# EVB-NORA-B2_SCHEM_0006_PinHeaders_ULED.net
KiCad netlist of a schematic drawn in Altium Designer
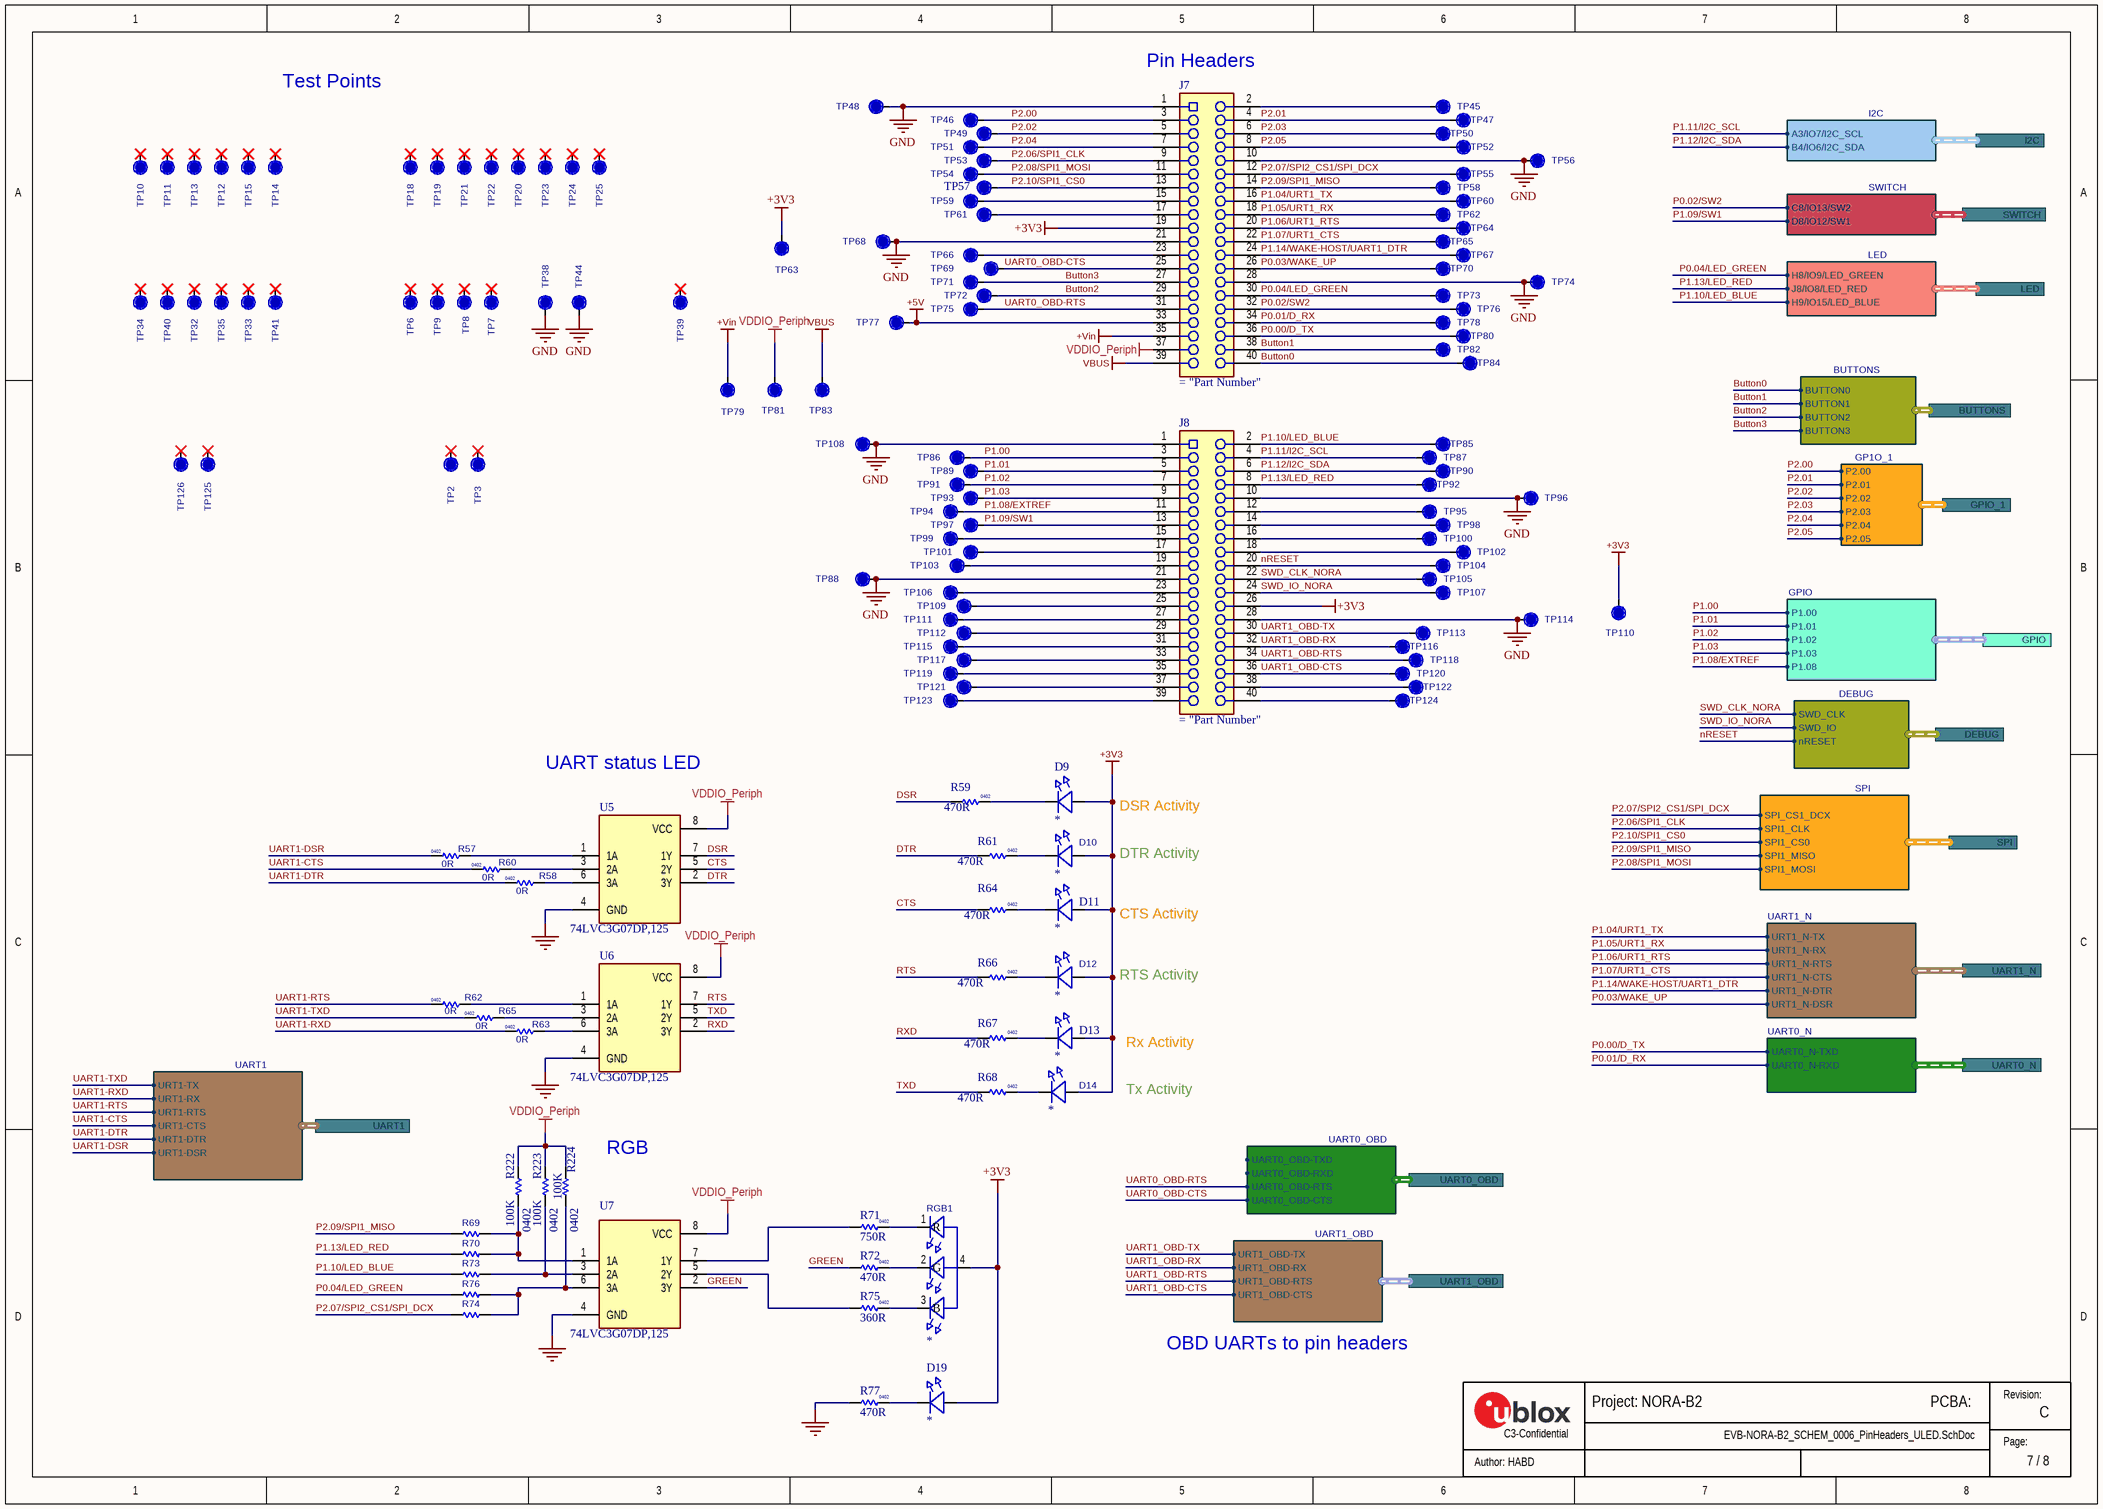
[diagram p0: EVB-NORA-B2_SCHEM_0006_PinHeaders_ULED.SchDoc]

(export (version "E")
  (design (tool "Eeschema 10.0.6"))
  (components
    (comp (ref "D9")
      (value "UBXH11-0000057")
      (footprint "LED_0603_YELLOW")
      (description "DIODE LED SMT YELLOW CLEAR LENS 2.1V 10MA 0603 YELLOW")
      (fields
        (field (name "COLOR") "*")
        (field (name "MANUFACTURER") "Lite-on Technology Corporation")
        (field (name "EDITOR") "eric.moog")
      )
      (libsource (lib "UBX_Parts_DB_Lib") (part "LED_BASE"))
    )
    (comp (ref "D10")
      (value "UBXH11-0000001")
      (footprint "LED_0603_GREEN")
      (description "LED SMD 0603 GREEN 2.5V 20mA")
      (fields
        (field (name "COLOR") "*")
        (field (name "MANUFACTURER") "Kingbright")
        (field (name "EDITOR") "gianni.falleroni")
        (field (name "RELEASED BY") "alex.claville")
      )
      (libsource (lib "UBX_Parts_DB_Lib") (part "LED_BASE"))
    )
    (comp (ref "D11")
      (value "UBXH11-0000057")
      (footprint "LED_0603_YELLOW")
      (description "DIODE LED SMT YELLOW CLEAR LENS 2.1V 10MA 0603 YELLOW")
      (fields
        (field (name "COLOR") "*")
        (field (name "MANUFACTURER") "Lite-on Technology Corporation")
        (field (name "EDITOR") "eric.moog")
      )
      (libsource (lib "UBX_Parts_DB_Lib") (part "LED_BASE"))
    )
    (comp (ref "D12")
      (value "UBXH11-0000001")
      (footprint "LED_0603_GREEN")
      (description "LED SMD 0603 GREEN 2.5V 20mA")
      (fields
        (field (name "COLOR") "*")
        (field (name "MANUFACTURER") "Kingbright")
        (field (name "EDITOR") "gianni.falleroni")
        (field (name "RELEASED BY") "alex.claville")
      )
      (libsource (lib "UBX_Parts_DB_Lib") (part "LED_BASE"))
    )
    (comp (ref "D13")
      (value "UBXH11-0000057")
      (footprint "LED_0603_YELLOW")
      (description "DIODE LED SMT YELLOW CLEAR LENS 2.1V 10MA 0603 YELLOW")
      (fields
        (field (name "COLOR") "*")
        (field (name "MANUFACTURER") "Lite-on Technology Corporation")
        (field (name "EDITOR") "eric.moog")
      )
      (libsource (lib "UBX_Parts_DB_Lib") (part "LED_BASE"))
    )
    (comp (ref "D14")
      (value "UBXH11-0000001")
      (footprint "LED_0603_GREEN")
      (description "LED SMD 0603 GREEN 2.5V 20mA")
      (fields
        (field (name "COLOR") "*")
        (field (name "MANUFACTURER") "Kingbright")
        (field (name "EDITOR") "gianni.falleroni")
        (field (name "RELEASED BY") "alex.claville")
      )
      (libsource (lib "UBX_Parts_DB_Lib") (part "LED_BASE"))
    )
    (comp (ref "D19")
      (value "UBXH11-0000018")
      (footprint "LED_0603_1600Lx800Wx400H_600x800Pad_800G_FLX")
      (description "LED CHIP 0603 LOW CURRENT OSRAM 0.002A GREEN 2.2V 2mA")
      (fields
        (field (name "COLOR") "*")
        (field (name "MANUFACTURER") "Osram")
        (field (name "EDITOR") "johann.furrer")
        (field (name "RELEASED BY") "martin.grasse")
      )
      (libsource (lib "UBX_Parts_DB_Lib") (part "LED_BASE"))
    )
    (comp (ref "J7")
      (value "~")
      (footprint "M208762042")
      (description "Connector")
      (fields
        (field (name "MANUFACTURER_PART_NUMBER") "M20-8762042")
        (field (name "MOUSER PART NUMBER") "855-M20-8762042")
      )
      (libsource (lib "SamacSys") (part "M20-8762042"))
    )
    (comp (ref "J8")
      (value "~")
      (footprint "M208762042")
      (description "Connector")
      (fields
        (field (name "MANUFACTURER_PART_NUMBER") "M20-8762042")
        (field (name "MOUSER PART NUMBER") "855-M20-8762042")
      )
      (libsource (lib "SamacSys") (part "M20-8762042"))
    )
    (comp (ref "R57")
      (value "0R")
      (footprint "RES 0402 HD")
      (description "RES THICK FILM CHIP 0402 0R 0 100mW")
      (fields
        (field (name "SIZE") "0402")
        (field (name "PART NUMBER") "UBXH18-0003002")
        (field (name "TOLERANCE") "0")
        (field (name "EDITOR") "charlotte.biber")
        (field (name "RELEASED BY") "peter.mueller")
      )
      (libsource (lib "UBX_Parts_DB_Lib") (part "Res sm"))
    )
    (comp (ref "R58")
      (value "0R")
      (footprint "RES 0402 HD")
      (description "RES THICK FILM CHIP 0402 0R 0 100mW")
      (fields
        (field (name "SIZE") "0402")
        (field (name "PART NUMBER") "UBXH18-0003002")
        (field (name "TOLERANCE") "0")
        (field (name "EDITOR") "charlotte.biber")
        (field (name "RELEASED BY") "peter.mueller")
      )
      (libsource (lib "UBX_Parts_DB_Lib") (part "Res sm"))
    )
    (comp (ref "R59")
      (value "470R")
      (footprint "RES_0402_1100Lx600Wx400H_500x600Pad_400G_FLX")
      (description "RES THICK FILM CHIP 0402 470R 5% 100mW")
      (fields
        (field (name "SIZE") "0402")
        (field (name "PART NUMBER") "UBXH18-0008041")
        (field (name "TOLERANCE") "5%")
        (field (name "EDITOR") "roland.rust")
        (field (name "RELEASED BY") "roland.rust")
      )
      (libsource (lib "UBX_Parts_DB_Lib") (part "Res sm"))
    )
    (comp (ref "R60")
      (value "0R")
      (footprint "RES 0402 HD")
      (description "RES THICK FILM CHIP 0402 0R 0 100mW")
      (fields
        (field (name "SIZE") "0402")
        (field (name "PART NUMBER") "UBXH18-0003002")
        (field (name "TOLERANCE") "0")
        (field (name "EDITOR") "charlotte.biber")
        (field (name "RELEASED BY") "peter.mueller")
      )
      (libsource (lib "UBX_Parts_DB_Lib") (part "Res sm"))
    )
    (comp (ref "R61")
      (value "470R")
      (footprint "RES_0402_1100Lx600Wx400H_500x600Pad_400G_FLX")
      (description "RES THICK FILM CHIP 0402 470R 5% 100mW")
      (fields
        (field (name "SIZE") "0402")
        (field (name "PART NUMBER") "UBXH18-0008041")
        (field (name "TOLERANCE") "5%")
        (field (name "EDITOR") "roland.rust")
        (field (name "RELEASED BY") "roland.rust")
      )
      (libsource (lib "UBX_Parts_DB_Lib") (part "Res sm"))
    )
    (comp (ref "R62")
      (value "0R")
      (footprint "RES 0402 HD")
      (description "RES THICK FILM CHIP 0402 0R 0 100mW")
      (fields
        (field (name "SIZE") "0402")
        (field (name "PART NUMBER") "UBXH18-0003002")
        (field (name "TOLERANCE") "0")
        (field (name "EDITOR") "charlotte.biber")
        (field (name "RELEASED BY") "peter.mueller")
      )
      (libsource (lib "UBX_Parts_DB_Lib") (part "Res sm"))
    )
    (comp (ref "R63")
      (value "0R")
      (footprint "RES 0402 HD")
      (description "RES THICK FILM CHIP 0402 0R 0 100mW")
      (fields
        (field (name "SIZE") "0402")
        (field (name "PART NUMBER") "UBXH18-0003002")
        (field (name "TOLERANCE") "0")
        (field (name "EDITOR") "charlotte.biber")
        (field (name "RELEASED BY") "peter.mueller")
      )
      (libsource (lib "UBX_Parts_DB_Lib") (part "Res sm"))
    )
    (comp (ref "R64")
      (value "470R")
      (footprint "RES_0402_1100Lx600Wx400H_500x600Pad_400G_FLX")
      (description "RES THICK FILM CHIP 0402 470R 5% 100mW")
      (fields
        (field (name "SIZE") "0402")
        (field (name "PART NUMBER") "UBXH18-0008041")
        (field (name "TOLERANCE") "5%")
        (field (name "EDITOR") "roland.rust")
        (field (name "RELEASED BY") "roland.rust")
      )
      (libsource (lib "UBX_Parts_DB_Lib") (part "Res sm"))
    )
    (comp (ref "R65")
      (value "0R")
      (footprint "RES 0402 HD")
      (description "RES THICK FILM CHIP 0402 0R 0 100mW")
      (fields
        (field (name "SIZE") "0402")
        (field (name "PART NUMBER") "UBXH18-0003002")
        (field (name "TOLERANCE") "0")
        (field (name "EDITOR") "charlotte.biber")
        (field (name "RELEASED BY") "peter.mueller")
      )
      (libsource (lib "UBX_Parts_DB_Lib") (part "Res sm"))
    )
    (comp (ref "R66")
      (value "470R")
      (footprint "RES_0402_1100Lx600Wx400H_500x600Pad_400G_FLX")
      (description "RES THICK FILM CHIP 0402 470R 5% 100mW")
      (fields
        (field (name "SIZE") "0402")
        (field (name "PART NUMBER") "UBXH18-0008041")
        (field (name "TOLERANCE") "5%")
        (field (name "EDITOR") "roland.rust")
        (field (name "RELEASED BY") "roland.rust")
      )
      (libsource (lib "UBX_Parts_DB_Lib") (part "Res sm"))
    )
    (comp (ref "R67")
      (value "470R")
      (footprint "RES_0402_1100Lx600Wx400H_500x600Pad_400G_FLX")
      (description "RES THICK FILM CHIP 0402 470R 5% 100mW")
      (fields
        (field (name "SIZE") "0402")
        (field (name "PART NUMBER") "UBXH18-0008041")
        (field (name "TOLERANCE") "5%")
        (field (name "EDITOR") "roland.rust")
        (field (name "RELEASED BY") "roland.rust")
      )
      (libsource (lib "UBX_Parts_DB_Lib") (part "Res sm"))
    )
    (comp (ref "R68")
      (value "470R")
      (footprint "RES_0402_1100Lx600Wx400H_500x600Pad_400G_FLX")
      (description "RES THICK FILM CHIP 0402 470R 5% 100mW")
      (fields
        (field (name "SIZE") "0402")
        (field (name "PART NUMBER") "UBXH18-0008041")
        (field (name "TOLERANCE") "5%")
        (field (name "EDITOR") "roland.rust")
        (field (name "RELEASED BY") "roland.rust")
      )
      (libsource (lib "UBX_Parts_DB_Lib") (part "Res sm"))
    )
    (comp (ref "R69")
      (value "UBXH18-0003002")
      (footprint "RES 0402 HD")
      (description "RES THICK FILM CHIP 0402 0R 0 100mW")
      (fields
        (field (name "TOLERANCE") "0")
        (field (name "MANUFACTURER") "KOA")
        (field (name "EDITOR") "charlotte.biber")
        (field (name "RELEASED BY") "peter.mueller")
      )
      (libsource (lib "UBX_Parts_DB_Lib") (part "Res sm"))
    )
    (comp (ref "R70")
      (value "UBXH18-0003002")
      (footprint "RES 0402 HD")
      (description "RES THICK FILM CHIP 0402 0R 0 100mW")
      (fields
        (field (name "TOLERANCE") "0")
        (field (name "MANUFACTURER") "KOA")
        (field (name "EDITOR") "charlotte.biber")
        (field (name "RELEASED BY") "peter.mueller")
      )
      (libsource (lib "UBX_Parts_DB_Lib") (part "Res sm"))
    )
    (comp (ref "R71")
      (value "750R")
      (footprint "RES_0402_1100Lx600Wx400H_500x600Pad_400G_FLX")
      (description "RES THICK FILM CHIP 0402 750R 5% 100mW")
      (fields
        (field (name "SIZE") "0402")
        (field (name "PART NUMBER") "UBXH18-0008046")
        (field (name "TOLERANCE") "5%")
        (field (name "EDITOR") "jaka.bevk")
        (field (name "RELEASED BY") "erian.bezhani")
      )
      (libsource (lib "UBX_Parts_DB_Lib") (part "Res sm"))
    )
    (comp (ref "R72")
      (value "470R")
      (footprint "RES_0402_1100Lx600Wx400H_500x600Pad_400G_FLX")
      (description "RES THICK FILM CHIP 0402 470R 5% 100mW")
      (fields
        (field (name "SIZE") "0402")
        (field (name "PART NUMBER") "UBXH18-0008041")
        (field (name "TOLERANCE") "5%")
        (field (name "EDITOR") "roland.rust")
        (field (name "RELEASED BY") "roland.rust")
      )
      (libsource (lib "UBX_Parts_DB_Lib") (part "Res sm"))
    )
    (comp (ref "R73")
      (value "UBXH18-0003002")
      (footprint "RES 0402 HD")
      (description "RES THICK FILM CHIP 0402 0R 0 100mW")
      (fields
        (field (name "TOLERANCE") "0")
        (field (name "MANUFACTURER") "KOA")
        (field (name "EDITOR") "charlotte.biber")
        (field (name "RELEASED BY") "peter.mueller")
      )
      (libsource (lib "UBX_Parts_DB_Lib") (part "Res sm"))
    )
    (comp (ref "R74")
      (value "UBXH18-0003002")
      (footprint "RES 0402 HD")
      (description "RES THICK FILM CHIP 0402 0R 0 100mW")
      (fields
        (field (name "TOLERANCE") "0")
        (field (name "MANUFACTURER") "KOA")
        (field (name "EDITOR") "charlotte.biber")
        (field (name "RELEASED BY") "peter.mueller")
      )
      (libsource (lib "UBX_Parts_DB_Lib") (part "Res sm"))
    )
    (comp (ref "R75")
      (value "360R")
      (footprint "RES_0402_1100Lx600Wx400H_500x600Pad_400G_FLX")
      (description "RES THICK FILM CHIP 0402 360R 1% 63mW")
      (fields
        (field (name "SIZE") "0402")
        (field (name "PART NUMBER") "UBXH18-0000216")
        (field (name "TOLERANCE") "1%")
        (field (name "EDITOR") "michael.hein")
        (field (name "RELEASED BY") "vasyl.dykyy")
      )
      (libsource (lib "UBX_Parts_DB_Lib") (part "Res sm"))
    )
    (comp (ref "R76")
      (value "UBXH18-0003002")
      (footprint "RES 0402 HD")
      (description "RES THICK FILM CHIP 0402 0R 0 100mW")
      (fields
        (field (name "TOLERANCE") "0")
        (field (name "MANUFACTURER") "KOA")
        (field (name "EDITOR") "charlotte.biber")
        (field (name "RELEASED BY") "peter.mueller")
      )
      (libsource (lib "UBX_Parts_DB_Lib") (part "Res sm"))
    )
    (comp (ref "R77")
      (value "470R")
      (footprint "RES_0402_1100Lx600Wx400H_500x600Pad_400G_FLX")
      (description "RES THICK FILM CHIP 0402 470R 5% 100mW")
      (fields
        (field (name "SIZE") "0402")
        (field (name "PART NUMBER") "UBXH18-0008041")
        (field (name "TOLERANCE") "5%")
        (field (name "EDITOR") "roland.rust")
        (field (name "RELEASED BY") "roland.rust")
      )
      (libsource (lib "UBX_Parts_DB_Lib") (part "Res sm"))
    )
    (comp (ref "R222")
      (value "100K")
      (footprint "RES 0402 HD")
      (description "RES THICK FILM CHIP 0402 100K 1% 63mW")
      (fields
        (field (name "SIZE") "0402")
        (field (name "PART NUMBER") "UBXH18-0000005")
        (field (name "TOLERANCE") "1%")
        (field (name "EDITOR") "dario.antonaz")
        (field (name "RELEASED BY") "sandro.sestan")
      )
      (libsource (lib "UBX_Parts_DB_Lib") (part "Res sm"))
    )
    (comp (ref "R223")
      (value "100K")
      (footprint "RES 0402 HD")
      (description "RES THICK FILM CHIP 0402 100K 1% 63mW")
      (fields
        (field (name "SIZE") "0402")
        (field (name "PART NUMBER") "UBXH18-0000005")
        (field (name "TOLERANCE") "1%")
        (field (name "EDITOR") "dario.antonaz")
        (field (name "RELEASED BY") "sandro.sestan")
      )
      (libsource (lib "UBX_Parts_DB_Lib") (part "Res sm"))
    )
    (comp (ref "R224")
      (value "100K")
      (footprint "RES 0402 HD")
      (description "RES THICK FILM CHIP 0402 100K 1% 63mW")
      (fields
        (field (name "SIZE") "0402")
        (field (name "PART NUMBER") "UBXH18-0000005")
        (field (name "TOLERANCE") "1%")
        (field (name "EDITOR") "dario.antonaz")
        (field (name "RELEASED BY") "sandro.sestan")
      )
      (libsource (lib "UBX_Parts_DB_Lib") (part "Res sm"))
    )
    (comp (ref "RGB1")
      (value "115-00026")
      (footprint "LED_1616")
      (description "LED RGB SMT 0606")
      (fields (field (name "COLOR") "*") (field (name "VOLTAGE") "None"))
      (libsource (lib "Arena_Parts_DB_Lib") (part "LED_RGB_CA_4"))
    )
    (comp (ref "TP2")
      (value "TP10R")
      (footprint "TP10R")
      (description "Testpoint, Round 1.0mm Dia")
      (fields (field (name "ADDED BY") "Jeremy D") (field (name "CHECKED BY") "Paul B"))
      (libsource (lib "LEGACY_Rigado_AltiumLib") (part "TP_R"))
    )
    (comp (ref "TP3")
      (value "TP10R")
      (footprint "TP10R")
      (description "Testpoint, Round 1.0mm Dia")
      (fields (field (name "ADDED BY") "Jeremy D") (field (name "CHECKED BY") "Paul B"))
      (libsource (lib "LEGACY_Rigado_AltiumLib") (part "TP_R"))
    )
    (comp (ref "TP6")
      (value "TP10R")
      (footprint "TP10R")
      (description "Testpoint, Round 1.0mm Dia")
      (fields (field (name "ADDED BY") "Jeremy D") (field (name "CHECKED BY") "Paul B"))
      (libsource (lib "") (part "TP_R_1"))
    )
    (comp (ref "TP7")
      (value "TP10R")
      (footprint "TP10R")
      (description "Testpoint, Round 1.0mm Dia")
      (fields (field (name "ADDED BY") "Jeremy D") (field (name "CHECKED BY") "Paul B"))
      (libsource (lib "LEGACY_Rigado_AltiumLib") (part "TP_R"))
    )
    (comp (ref "TP8")
      (value "TP10R")
      (footprint "TP10R")
      (description "Testpoint, Round 1.0mm Dia")
      (fields (field (name "ADDED BY") "Jeremy D") (field (name "CHECKED BY") "Paul B"))
      (libsource (lib "LEGACY_Rigado_AltiumLib") (part "TP_R"))
    )
    (comp (ref "TP9")
      (value "TP10R")
      (footprint "TP10R")
      (description "Testpoint, Round 1.0mm Dia")
      (fields (field (name "ADDED BY") "Jeremy D") (field (name "CHECKED BY") "Paul B"))
      (libsource (lib "LEGACY_Rigado_AltiumLib") (part "TP_R"))
    )
    (comp (ref "TP10")
      (value "TP10R")
      (footprint "TP10R")
      (description "Testpoint, Round 1.0mm Dia")
      (fields (field (name "ADDED BY") "Jeremy D") (field (name "CHECKED BY") "Paul B"))
      (libsource (lib "LEGACY_Rigado_AltiumLib") (part "TP_R"))
    )
    (comp (ref "TP11")
      (value "TP10R")
      (footprint "TP10R")
      (description "Testpoint, Round 1.0mm Dia")
      (fields (field (name "ADDED BY") "Jeremy D") (field (name "CHECKED BY") "Paul B"))
      (libsource (lib "LEGACY_Rigado_AltiumLib") (part "TP_R"))
    )
    (comp (ref "TP12")
      (value "TP10R")
      (footprint "TP10R")
      (description "Testpoint, Round 1.0mm Dia")
      (fields (field (name "ADDED BY") "Jeremy D") (field (name "CHECKED BY") "Paul B"))
      (libsource (lib "LEGACY_Rigado_AltiumLib") (part "TP_R"))
    )
    (comp (ref "TP13")
      (value "TP10R")
      (footprint "TP10R")
      (description "Testpoint, Round 1.0mm Dia")
      (fields (field (name "ADDED BY") "Jeremy D") (field (name "CHECKED BY") "Paul B"))
      (libsource (lib "LEGACY_Rigado_AltiumLib") (part "TP_R"))
    )
    (comp (ref "TP14")
      (value "TP10R")
      (footprint "TP10R")
      (description "Testpoint, Round 1.0mm Dia")
      (fields (field (name "ADDED BY") "Jeremy D") (field (name "CHECKED BY") "Paul B"))
      (libsource (lib "LEGACY_Rigado_AltiumLib") (part "TP_R"))
    )
    (comp (ref "TP15")
      (value "TP10R")
      (footprint "TP10R")
      (description "Testpoint, Round 1.0mm Dia")
      (fields (field (name "ADDED BY") "Jeremy D") (field (name "CHECKED BY") "Paul B"))
      (libsource (lib "LEGACY_Rigado_AltiumLib") (part "TP_R"))
    )
    (comp (ref "TP18")
      (value "TP10R")
      (footprint "TP10R")
      (description "Testpoint, Round 1.0mm Dia")
      (fields (field (name "ADDED BY") "Jeremy D") (field (name "CHECKED BY") "Paul B"))
      (libsource (lib "LEGACY_Rigado_AltiumLib") (part "TP_R"))
    )
    (comp (ref "TP19")
      (value "TP10R")
      (footprint "TP10R")
      (description "Testpoint, Round 1.0mm Dia")
      (fields (field (name "ADDED BY") "Jeremy D") (field (name "CHECKED BY") "Paul B"))
      (libsource (lib "LEGACY_Rigado_AltiumLib") (part "TP_R"))
    )
    (comp (ref "TP20")
      (value "TP10R")
      (footprint "TP10R")
      (description "Testpoint, Round 1.0mm Dia")
      (fields (field (name "ADDED BY") "Jeremy D") (field (name "CHECKED BY") "Paul B"))
      (libsource (lib "LEGACY_Rigado_AltiumLib") (part "TP_R"))
    )
    (comp (ref "TP21")
      (value "TP10R")
      (footprint "TP10R")
      (description "Testpoint, Round 1.0mm Dia")
      (fields (field (name "ADDED BY") "Jeremy D") (field (name "CHECKED BY") "Paul B"))
      (libsource (lib "LEGACY_Rigado_AltiumLib") (part "TP_R"))
    )
    (comp (ref "TP22")
      (value "TP10R")
      (footprint "TP10R")
      (description "Testpoint, Round 1.0mm Dia")
      (fields (field (name "ADDED BY") "Jeremy D") (field (name "CHECKED BY") "Paul B"))
      (libsource (lib "LEGACY_Rigado_AltiumLib") (part "TP_R"))
    )
    (comp (ref "TP23")
      (value "TP10R")
      (footprint "TP10R")
      (description "Testpoint, Round 1.0mm Dia")
      (fields (field (name "ADDED BY") "Jeremy D") (field (name "CHECKED BY") "Paul B"))
      (libsource (lib "LEGACY_Rigado_AltiumLib") (part "TP_R"))
    )
    (comp (ref "TP24")
      (value "TP10R")
      (footprint "TP10R")
      (description "Testpoint, Round 1.0mm Dia")
      (fields (field (name "ADDED BY") "Jeremy D") (field (name "CHECKED BY") "Paul B"))
      (libsource (lib "LEGACY_Rigado_AltiumLib") (part "TP_R"))
    )
    (comp (ref "TP25")
      (value "TP10R")
      (footprint "TP10R")
      (description "Testpoint, Round 1.0mm Dia")
      (fields (field (name "ADDED BY") "Jeremy D") (field (name "CHECKED BY") "Paul B"))
      (libsource (lib "LEGACY_Rigado_AltiumLib") (part "TP_R"))
    )
    (comp (ref "TP32")
      (value "TP10R")
      (footprint "TP10R")
      (description "Testpoint, Round 1.0mm Dia")
      (fields (field (name "ADDED BY") "Jeremy D") (field (name "CHECKED BY") "Paul B"))
      (libsource (lib "LEGACY_Rigado_AltiumLib") (part "TP_R"))
    )
    (comp (ref "TP33")
      (value "TP10R")
      (footprint "TP10R")
      (description "Testpoint, Round 1.0mm Dia")
      (fields (field (name "ADDED BY") "Jeremy D") (field (name "CHECKED BY") "Paul B"))
      (libsource (lib "LEGACY_Rigado_AltiumLib") (part "TP_R"))
    )
    (comp (ref "TP34")
      (value "TP10R")
      (footprint "TP10R")
      (description "Testpoint, Round 1.0mm Dia")
      (fields (field (name "ADDED BY") "Jeremy D") (field (name "CHECKED BY") "Paul B"))
      (libsource (lib "LEGACY_Rigado_AltiumLib") (part "TP_R"))
    )
    (comp (ref "TP35")
      (value "TP10R")
      (footprint "TP10R")
      (description "Testpoint, Round 1.0mm Dia")
      (fields (field (name "ADDED BY") "Jeremy D") (field (name "CHECKED BY") "Paul B"))
      (libsource (lib "LEGACY_Rigado_AltiumLib") (part "TP_R"))
    )
    (comp (ref "TP38")
      (value "TP10R")
      (footprint "TP10R")
      (description "Testpoint, Round 1.0mm Dia")
      (fields (field (name "ADDED BY") "Jeremy D") (field (name "CHECKED BY") "Paul B"))
      (libsource (lib "LEGACY_Rigado_AltiumLib") (part "TP_R"))
    )
    (comp (ref "TP39")
      (value "TP10R")
      (footprint "TP10R")
      (description "Testpoint, Round 1.0mm Dia")
      (fields (field (name "ADDED BY") "Jeremy D") (field (name "CHECKED BY") "Paul B"))
      (libsource (lib "LEGACY_Rigado_AltiumLib") (part "TP_R"))
    )
    (comp (ref "TP40")
      (value "TP10R")
      (footprint "TP10R")
      (description "Testpoint, Round 1.0mm Dia")
      (fields (field (name "ADDED BY") "Jeremy D") (field (name "CHECKED BY") "Paul B"))
      (libsource (lib "LEGACY_Rigado_AltiumLib") (part "TP_R"))
    )
    (comp (ref "TP41")
      (value "TP10R")
      (footprint "TP10R")
      (description "Testpoint, Round 1.0mm Dia")
      (fields (field (name "ADDED BY") "Jeremy D") (field (name "CHECKED BY") "Paul B"))
      (libsource (lib "LEGACY_Rigado_AltiumLib") (part "TP_R"))
    )
    (comp (ref "TP44")
      (value "TP10R")
      (footprint "TP10R")
      (description "Testpoint, Round 1.0mm Dia")
      (fields (field (name "ADDED BY") "Jeremy D") (field (name "CHECKED BY") "Paul B"))
      (libsource (lib "LEGACY_Rigado_AltiumLib") (part "TP_R"))
    )
    (comp (ref "TP45")
      (value "TP10R")
      (footprint "TP10R")
      (description "Testpoint, Round 1.0mm Dia")
      (fields (field (name "ADDED BY") "Jeremy D") (field (name "CHECKED BY") "Paul B"))
      (libsource (lib "LEGACY_Rigado_AltiumLib") (part "TP_R"))
    )
    (comp (ref "TP46")
      (value "TP10R")
      (footprint "TP10R")
      (description "Testpoint, Round 1.0mm Dia")
      (fields (field (name "ADDED BY") "Jeremy D") (field (name "CHECKED BY") "Paul B"))
      (libsource (lib "LEGACY_Rigado_AltiumLib") (part "TP_R"))
    )
    (comp (ref "TP47")
      (value "TP10R")
      (footprint "TP10R")
      (description "Testpoint, Round 1.0mm Dia")
      (fields (field (name "ADDED BY") "Jeremy D") (field (name "CHECKED BY") "Paul B"))
      (libsource (lib "") (part "TP_R_1"))
    )
    (comp (ref "TP48")
      (value "TP10R")
      (footprint "TP10R")
      (description "Testpoint, Round 1.0mm Dia")
      (fields (field (name "ADDED BY") "Jeremy D") (field (name "CHECKED BY") "Paul B"))
      (libsource (lib "LEGACY_Rigado_AltiumLib") (part "TP_R"))
    )
    (comp (ref "TP49")
      (value "TP10R")
      (footprint "TP10R")
      (description "Testpoint, Round 1.0mm Dia")
      (fields (field (name "ADDED BY") "Jeremy D") (field (name "CHECKED BY") "Paul B"))
      (libsource (lib "LEGACY_Rigado_AltiumLib") (part "TP_R"))
    )
    (comp (ref "TP50")
      (value "TP10R")
      (footprint "TP10R")
      (description "Testpoint, Round 1.0mm Dia")
      (fields (field (name "ADDED BY") "Jeremy D") (field (name "CHECKED BY") "Paul B"))
      (libsource (lib "") (part "TP_R_1"))
    )
    (comp (ref "TP51")
      (value "TP10R")
      (footprint "TP10R")
      (description "Testpoint, Round 1.0mm Dia")
      (fields (field (name "ADDED BY") "Jeremy D") (field (name "CHECKED BY") "Paul B"))
      (libsource (lib "LEGACY_Rigado_AltiumLib") (part "TP_R"))
    )
    (comp (ref "TP52")
      (value "TP10R")
      (footprint "TP10R")
      (description "Testpoint, Round 1.0mm Dia")
      (fields (field (name "ADDED BY") "Jeremy D") (field (name "CHECKED BY") "Paul B"))
      (libsource (lib "LEGACY_Rigado_AltiumLib") (part "TP_R"))
    )
    (comp (ref "TP53")
      (value "TP10R")
      (footprint "TP10R")
      (description "Testpoint, Round 1.0mm Dia")
      (fields (field (name "ADDED BY") "Jeremy D") (field (name "CHECKED BY") "Paul B"))
      (libsource (lib "LEGACY_Rigado_AltiumLib") (part "TP_R"))
    )
    (comp (ref "TP54")
      (value "TP10R")
      (footprint "TP10R")
      (description "Testpoint, Round 1.0mm Dia")
      (fields (field (name "ADDED BY") "Jeremy D") (field (name "CHECKED BY") "Paul B"))
      (libsource (lib "LEGACY_Rigado_AltiumLib") (part "TP_R"))
    )
    (comp (ref "TP55")
      (value "TP10R")
      (footprint "TP10R")
      (description "Testpoint, Round 1.0mm Dia")
      (fields (field (name "ADDED BY") "Jeremy D") (field (name "CHECKED BY") "Paul B"))
      (libsource (lib "LEGACY_Rigado_AltiumLib") (part "TP_R"))
    )
    (comp (ref "TP56")
      (value "TP10R")
      (footprint "TP10R")
      (description "Testpoint, Round 1.0mm Dia")
      (fields (field (name "ADDED BY") "Jeremy D") (field (name "CHECKED BY") "Paul B"))
      (libsource (lib "LEGACY_Rigado_AltiumLib") (part "TP_R"))
    )
    (comp (ref "TP57")
      (value "TP10R")
      (footprint "TP10R")
      (description "Testpoint, Round 1.0mm Dia")
      (fields (field (name "ADDED BY") "Jeremy D") (field (name "CHECKED BY") "Paul B"))
      (libsource (lib "LEGACY_Rigado_AltiumLib") (part "TP_R"))
    )
    (comp (ref "TP58")
      (value "TP10R")
      (footprint "TP10R")
      (description "Testpoint, Round 1.0mm Dia")
      (fields (field (name "ADDED BY") "Jeremy D") (field (name "CHECKED BY") "Paul B"))
      (libsource (lib "LEGACY_Rigado_AltiumLib") (part "TP_R"))
    )
    (comp (ref "TP59")
      (value "TP10R")
      (footprint "TP10R")
      (description "Testpoint, Round 1.0mm Dia")
      (fields (field (name "ADDED BY") "Jeremy D") (field (name "CHECKED BY") "Paul B"))
      (libsource (lib "LEGACY_Rigado_AltiumLib") (part "TP_R"))
    )
    (comp (ref "TP60")
      (value "TP10R")
      (footprint "TP10R")
      (description "Testpoint, Round 1.0mm Dia")
      (fields (field (name "ADDED BY") "Jeremy D") (field (name "CHECKED BY") "Paul B"))
      (libsource (lib "LEGACY_Rigado_AltiumLib") (part "TP_R"))
    )
    (comp (ref "TP61")
      (value "TP10R")
      (footprint "TP10R")
      (description "Testpoint, Round 1.0mm Dia")
      (fields (field (name "ADDED BY") "Jeremy D") (field (name "CHECKED BY") "Paul B"))
      (libsource (lib "LEGACY_Rigado_AltiumLib") (part "TP_R"))
    )
    (comp (ref "TP62")
      (value "TP10R")
      (footprint "TP10R")
      (description "Testpoint, Round 1.0mm Dia")
      (fields (field (name "ADDED BY") "Jeremy D") (field (name "CHECKED BY") "Paul B"))
      (libsource (lib "LEGACY_Rigado_AltiumLib") (part "TP_R"))
    )
    (comp (ref "TP63")
      (value "TP10R")
      (footprint "TP10R")
      (description "Testpoint, Round 1.0mm Dia")
      (fields (field (name "ADDED BY") "Jeremy D") (field (name "CHECKED BY") "Paul B"))
      (libsource (lib "LEGACY_Rigado_AltiumLib") (part "TP_R"))
    )
    (comp (ref "TP64")
      (value "TP10R")
      (footprint "TP10R")
      (description "Testpoint, Round 1.0mm Dia")
      (fields (field (name "ADDED BY") "Jeremy D") (field (name "CHECKED BY") "Paul B"))
      (libsource (lib "") (part "TP_R_1"))
    )
    (comp (ref "TP65")
      (value "TP10R")
      (footprint "TP10R")
      (description "Testpoint, Round 1.0mm Dia")
      (fields (field (name "ADDED BY") "Jeremy D") (field (name "CHECKED BY") "Paul B"))
      (libsource (lib "") (part "TP_R_1"))
    )
    (comp (ref "TP66")
      (value "TP10R")
      (footprint "TP10R")
      (description "Testpoint, Round 1.0mm Dia")
      (fields (field (name "ADDED BY") "Jeremy D") (field (name "CHECKED BY") "Paul B"))
      (libsource (lib "LEGACY_Rigado_AltiumLib") (part "TP_R"))
    )
    (comp (ref "TP67")
      (value "TP10R")
      (footprint "TP10R")
      (description "Testpoint, Round 1.0mm Dia")
      (fields (field (name "ADDED BY") "Jeremy D") (field (name "CHECKED BY") "Paul B"))
      (libsource (lib "") (part "TP_R_1"))
    )
    (comp (ref "TP68")
      (value "TP10R")
      (footprint "TP10R")
      (description "Testpoint, Round 1.0mm Dia")
      (fields (field (name "ADDED BY") "Jeremy D") (field (name "CHECKED BY") "Paul B"))
      (libsource (lib "LEGACY_Rigado_AltiumLib") (part "TP_R"))
    )
    (comp (ref "TP69")
      (value "TP10R")
      (footprint "TP10R")
      (description "Testpoint, Round 1.0mm Dia")
      (fields (field (name "ADDED BY") "Jeremy D") (field (name "CHECKED BY") "Paul B"))
      (libsource (lib "LEGACY_Rigado_AltiumLib") (part "TP_R"))
    )
    (comp (ref "TP70")
      (value "TP10R")
      (footprint "TP10R")
      (description "Testpoint, Round 1.0mm Dia")
      (fields (field (name "ADDED BY") "Jeremy D") (field (name "CHECKED BY") "Paul B"))
      (libsource (lib "LEGACY_Rigado_AltiumLib") (part "TP_R"))
    )
    (comp (ref "TP71")
      (value "TP10R")
      (footprint "TP10R")
      (description "Testpoint, Round 1.0mm Dia")
      (fields (field (name "ADDED BY") "Jeremy D") (field (name "CHECKED BY") "Paul B"))
      (libsource (lib "LEGACY_Rigado_AltiumLib") (part "TP_R"))
    )
    (comp (ref "TP72")
      (value "TP10R")
      (footprint "TP10R")
      (description "Testpoint, Round 1.0mm Dia")
      (fields (field (name "ADDED BY") "Jeremy D") (field (name "CHECKED BY") "Paul B"))
      (libsource (lib "LEGACY_Rigado_AltiumLib") (part "TP_R"))
    )
    (comp (ref "TP73")
      (value "TP10R")
      (footprint "TP10R")
      (description "Testpoint, Round 1.0mm Dia")
      (fields (field (name "ADDED BY") "Jeremy D") (field (name "CHECKED BY") "Paul B"))
      (libsource (lib "") (part "TP_R_1"))
    )
    (comp (ref "TP74")
      (value "TP10R")
      (footprint "TP10R")
      (description "Testpoint, Round 1.0mm Dia")
      (fields (field (name "ADDED BY") "Jeremy D") (field (name "CHECKED BY") "Paul B"))
      (libsource (lib "") (part "TP_R_1"))
    )
    (comp (ref "TP75")
      (value "TP10R")
      (footprint "TP10R")
      (description "Testpoint, Round 1.0mm Dia")
      (fields (field (name "ADDED BY") "Jeremy D") (field (name "CHECKED BY") "Paul B"))
      (libsource (lib "LEGACY_Rigado_AltiumLib") (part "TP_R"))
    )
    (comp (ref "TP76")
      (value "TP10R")
      (footprint "TP10R")
      (description "Testpoint, Round 1.0mm Dia")
      (fields (field (name "ADDED BY") "Jeremy D") (field (name "CHECKED BY") "Paul B"))
      (libsource (lib "") (part "TP_R_1"))
    )
    (comp (ref "TP77")
      (value "TP10R")
      (footprint "TP10R")
      (description "Testpoint, Round 1.0mm Dia")
      (fields (field (name "ADDED BY") "Jeremy D") (field (name "CHECKED BY") "Paul B"))
      (libsource (lib "LEGACY_Rigado_AltiumLib") (part "TP_R"))
    )
    (comp (ref "TP78")
      (value "TP10R")
      (footprint "TP10R")
      (description "Testpoint, Round 1.0mm Dia")
      (fields (field (name "ADDED BY") "Jeremy D") (field (name "CHECKED BY") "Paul B"))
      (libsource (lib "") (part "TP_R_1"))
    )
    (comp (ref "TP79")
      (value "TP10R")
      (footprint "TP10R")
      (description "Testpoint, Round 1.0mm Dia")
      (fields (field (name "ADDED BY") "Jeremy D") (field (name "CHECKED BY") "Paul B"))
      (libsource (lib "LEGACY_Rigado_AltiumLib") (part "TP_R"))
    )
    (comp (ref "TP80")
      (value "TP10R")
      (footprint "TP10R")
      (description "Testpoint, Round 1.0mm Dia")
      (fields (field (name "ADDED BY") "Jeremy D") (field (name "CHECKED BY") "Paul B"))
      (libsource (lib "") (part "TP_R_1"))
    )
    (comp (ref "TP81")
      (value "TP10R")
      (footprint "TP10R")
      (description "Testpoint, Round 1.0mm Dia")
      (fields (field (name "ADDED BY") "Jeremy D") (field (name "CHECKED BY") "Paul B"))
      (libsource (lib "LEGACY_Rigado_AltiumLib") (part "TP_R"))
    )
    (comp (ref "TP82")
      (value "TP10R")
      (footprint "TP10R")
      (description "Testpoint, Round 1.0mm Dia")
      (fields (field (name "ADDED BY") "Jeremy D") (field (name "CHECKED BY") "Paul B"))
      (libsource (lib "") (part "TP_R_1"))
    )
    (comp (ref "TP83")
      (value "TP10R")
      (footprint "TP10R")
      (description "Testpoint, Round 1.0mm Dia")
      (fields (field (name "ADDED BY") "Jeremy D") (field (name "CHECKED BY") "Paul B"))
      (libsource (lib "LEGACY_Rigado_AltiumLib") (part "TP_R"))
    )
    (comp (ref "TP84")
      (value "TP10R")
      (footprint "TP10R")
      (description "Testpoint, Round 1.0mm Dia")
      (fields (field (name "ADDED BY") "Jeremy D") (field (name "CHECKED BY") "Paul B"))
      (libsource (lib "") (part "TP_R_1"))
    )
    (comp (ref "TP85")
      (value "TP10R")
      (footprint "TP10R")
      (description "Testpoint, Round 1.0mm Dia")
      (fields (field (name "ADDED BY") "Jeremy D") (field (name "CHECKED BY") "Paul B"))
      (libsource (lib "") (part "TP_R_1"))
    )
    (comp (ref "TP86")
      (value "TP10R")
      (footprint "TP10R")
      (description "Testpoint, Round 1.0mm Dia")
      (fields (field (name "ADDED BY") "Jeremy D") (field (name "CHECKED BY") "Paul B"))
      (libsource (lib "LEGACY_Rigado_AltiumLib") (part "TP_R"))
    )
    (comp (ref "TP87")
      (value "TP10R")
      (footprint "TP10R")
      (description "Testpoint, Round 1.0mm Dia")
      (fields (field (name "ADDED BY") "Jeremy D") (field (name "CHECKED BY") "Paul B"))
      (libsource (lib "") (part "TP_R_1"))
    )
    (comp (ref "TP88")
      (value "TP10R")
      (footprint "TP10R")
      (description "Testpoint, Round 1.0mm Dia")
      (fields (field (name "ADDED BY") "Jeremy D") (field (name "CHECKED BY") "Paul B"))
      (libsource (lib "LEGACY_Rigado_AltiumLib") (part "TP_R"))
    )
    (comp (ref "TP89")
      (value "TP10R")
      (footprint "TP10R")
      (description "Testpoint, Round 1.0mm Dia")
      (fields (field (name "ADDED BY") "Jeremy D") (field (name "CHECKED BY") "Paul B"))
      (libsource (lib "LEGACY_Rigado_AltiumLib") (part "TP_R"))
    )
    (comp (ref "TP90")
      (value "TP10R")
      (footprint "TP10R")
      (description "Testpoint, Round 1.0mm Dia")
      (fields (field (name "ADDED BY") "Jeremy D") (field (name "CHECKED BY") "Paul B"))
      (libsource (lib "") (part "TP_R_1"))
    )
    (comp (ref "TP91")
      (value "TP10R")
      (footprint "TP10R")
      (description "Testpoint, Round 1.0mm Dia")
      (fields (field (name "ADDED BY") "Jeremy D") (field (name "CHECKED BY") "Paul B"))
      (libsource (lib "LEGACY_Rigado_AltiumLib") (part "TP_R"))
    )
    (comp (ref "TP92")
      (value "TP10R")
      (footprint "TP10R")
      (description "Testpoint, Round 1.0mm Dia")
      (fields (field (name "ADDED BY") "Jeremy D") (field (name "CHECKED BY") "Paul B"))
      (libsource (lib "LEGACY_Rigado_AltiumLib") (part "TP_R"))
    )
    (comp (ref "TP93")
      (value "TP10R")
      (footprint "TP10R")
      (description "Testpoint, Round 1.0mm Dia")
      (fields (field (name "ADDED BY") "Jeremy D") (field (name "CHECKED BY") "Paul B"))
      (libsource (lib "LEGACY_Rigado_AltiumLib") (part "TP_R"))
    )
    (comp (ref "TP94")
      (value "TP10R")
      (footprint "TP10R")
      (description "Testpoint, Round 1.0mm Dia")
      (fields (field (name "ADDED BY") "Jeremy D") (field (name "CHECKED BY") "Paul B"))
      (libsource (lib "LEGACY_Rigado_AltiumLib") (part "TP_R"))
    )
    (comp (ref "TP95")
      (value "TP10R")
      (footprint "TP10R")
      (description "Testpoint, Round 1.0mm Dia")
      (fields (field (name "ADDED BY") "Jeremy D") (field (name "CHECKED BY") "Paul B"))
      (libsource (lib "LEGACY_Rigado_AltiumLib") (part "TP_R"))
    )
    (comp (ref "TP96")
      (value "TP10R")
      (footprint "TP10R")
      (description "Testpoint, Round 1.0mm Dia")
      (fields (field (name "ADDED BY") "Jeremy D") (field (name "CHECKED BY") "Paul B"))
      (libsource (lib "") (part "TP_R_1"))
    )
    (comp (ref "TP97")
      (value "TP10R")
      (footprint "TP10R")
      (description "Testpoint, Round 1.0mm Dia")
      (fields (field (name "ADDED BY") "Jeremy D") (field (name "CHECKED BY") "Paul B"))
      (libsource (lib "LEGACY_Rigado_AltiumLib") (part "TP_R"))
    )
    (comp (ref "TP98")
      (value "TP10R")
      (footprint "TP10R")
      (description "Testpoint, Round 1.0mm Dia")
      (fields (field (name "ADDED BY") "Jeremy D") (field (name "CHECKED BY") "Paul B"))
      (libsource (lib "LEGACY_Rigado_AltiumLib") (part "TP_R"))
    )
    (comp (ref "TP99")
      (value "TP10R")
      (footprint "TP10R")
      (description "Testpoint, Round 1.0mm Dia")
      (fields (field (name "ADDED BY") "Jeremy D") (field (name "CHECKED BY") "Paul B"))
      (libsource (lib "LEGACY_Rigado_AltiumLib") (part "TP_R"))
    )
    (comp (ref "TP100")
      (value "TP10R")
      (footprint "TP10R")
      (description "Testpoint, Round 1.0mm Dia")
      (fields (field (name "ADDED BY") "Jeremy D") (field (name "CHECKED BY") "Paul B"))
      (libsource (lib "LEGACY_Rigado_AltiumLib") (part "TP_R"))
    )
    (comp (ref "TP101")
      (value "TP10R")
      (footprint "TP10R")
      (description "Testpoint, Round 1.0mm Dia")
      (fields (field (name "ADDED BY") "Jeremy D") (field (name "CHECKED BY") "Paul B"))
      (libsource (lib "LEGACY_Rigado_AltiumLib") (part "TP_R"))
    )
    (comp (ref "TP102")
      (value "TP10R")
      (footprint "TP10R")
      (description "Testpoint, Round 1.0mm Dia")
      (fields (field (name "ADDED BY") "Jeremy D") (field (name "CHECKED BY") "Paul B"))
      (libsource (lib "LEGACY_Rigado_AltiumLib") (part "TP_R"))
    )
    (comp (ref "TP103")
      (value "TP10R")
      (footprint "TP10R")
      (description "Testpoint, Round 1.0mm Dia")
      (fields (field (name "ADDED BY") "Jeremy D") (field (name "CHECKED BY") "Paul B"))
      (libsource (lib "LEGACY_Rigado_AltiumLib") (part "TP_R"))
    )
    (comp (ref "TP104")
      (value "TP10R")
      (footprint "TP10R")
      (description "Testpoint, Round 1.0mm Dia")
      (fields (field (name "ADDED BY") "Jeremy D") (field (name "CHECKED BY") "Paul B"))
      (libsource (lib "LEGACY_Rigado_AltiumLib") (part "TP_R"))
    )
    (comp (ref "TP105")
      (value "TP10R")
      (footprint "TP10R")
      (description "Testpoint, Round 1.0mm Dia")
      (fields (field (name "ADDED BY") "Jeremy D") (field (name "CHECKED BY") "Paul B"))
      (libsource (lib "LEGACY_Rigado_AltiumLib") (part "TP_R"))
    )
    (comp (ref "TP106")
      (value "TP10R")
      (footprint "TP10R")
      (description "Testpoint, Round 1.0mm Dia")
      (fields (field (name "ADDED BY") "Jeremy D") (field (name "CHECKED BY") "Paul B"))
      (libsource (lib "LEGACY_Rigado_AltiumLib") (part "TP_R"))
    )
    (comp (ref "TP107")
      (value "TP10R")
      (footprint "TP10R")
      (description "Testpoint, Round 1.0mm Dia")
      (fields (field (name "ADDED BY") "Jeremy D") (field (name "CHECKED BY") "Paul B"))
      (libsource (lib "LEGACY_Rigado_AltiumLib") (part "TP_R"))
    )
    (comp (ref "TP108")
      (value "TP10R")
      (footprint "TP10R")
      (description "Testpoint, Round 1.0mm Dia")
      (fields (field (name "ADDED BY") "Jeremy D") (field (name "CHECKED BY") "Paul B"))
      (libsource (lib "LEGACY_Rigado_AltiumLib") (part "TP_R"))
    )
    (comp (ref "TP109")
      (value "TP10R")
      (footprint "TP10R")
      (description "Testpoint, Round 1.0mm Dia")
      (fields (field (name "ADDED BY") "Jeremy D") (field (name "CHECKED BY") "Paul B"))
      (libsource (lib "LEGACY_Rigado_AltiumLib") (part "TP_R"))
    )
    (comp (ref "TP110")
      (value "TP10R")
      (footprint "TP10R")
      (description "Testpoint, Round 1.0mm Dia")
      (fields (field (name "ADDED BY") "Jeremy D") (field (name "CHECKED BY") "Paul B"))
      (libsource (lib "LEGACY_Rigado_AltiumLib") (part "TP_R"))
    )
    (comp (ref "TP111")
      (value "TP10R")
      (footprint "TP10R")
      (description "Testpoint, Round 1.0mm Dia")
      (fields (field (name "ADDED BY") "Jeremy D") (field (name "CHECKED BY") "Paul B"))
      (libsource (lib "LEGACY_Rigado_AltiumLib") (part "TP_R"))
    )
    (comp (ref "TP112")
      (value "TP10R")
      (footprint "TP10R")
      (description "Testpoint, Round 1.0mm Dia")
      (fields (field (name "ADDED BY") "Jeremy D") (field (name "CHECKED BY") "Paul B"))
      (libsource (lib "LEGACY_Rigado_AltiumLib") (part "TP_R"))
    )
    (comp (ref "TP113")
      (value "TP10R")
      (footprint "TP10R")
      (description "Testpoint, Round 1.0mm Dia")
      (fields (field (name "ADDED BY") "Jeremy D") (field (name "CHECKED BY") "Paul B"))
      (libsource (lib "LEGACY_Rigado_AltiumLib") (part "TP_R"))
    )
    (comp (ref "TP114")
      (value "TP10R")
      (footprint "TP10R")
      (description "Testpoint, Round 1.0mm Dia")
      (fields (field (name "ADDED BY") "Jeremy D") (field (name "CHECKED BY") "Paul B"))
      (libsource (lib "") (part "TP_R_1"))
    )
    (comp (ref "TP115")
      (value "TP10R")
      (footprint "TP10R")
      (description "Testpoint, Round 1.0mm Dia")
      (fields (field (name "ADDED BY") "Jeremy D") (field (name "CHECKED BY") "Paul B"))
      (libsource (lib "LEGACY_Rigado_AltiumLib") (part "TP_R"))
    )
    (comp (ref "TP116")
      (value "TP10R")
      (footprint "TP10R")
      (description "Testpoint, Round 1.0mm Dia")
      (fields (field (name "ADDED BY") "Jeremy D") (field (name "CHECKED BY") "Paul B"))
      (libsource (lib "LEGACY_Rigado_AltiumLib") (part "TP_R"))
    )
    (comp (ref "TP117")
      (value "TP10R")
      (footprint "TP10R")
      (description "Testpoint, Round 1.0mm Dia")
      (fields (field (name "ADDED BY") "Jeremy D") (field (name "CHECKED BY") "Paul B"))
      (libsource (lib "LEGACY_Rigado_AltiumLib") (part "TP_R"))
    )
    (comp (ref "TP118")
      (value "TP10R")
      (footprint "TP10R")
      (description "Testpoint, Round 1.0mm Dia")
      (fields (field (name "ADDED BY") "Jeremy D") (field (name "CHECKED BY") "Paul B"))
      (libsource (lib "LEGACY_Rigado_AltiumLib") (part "TP_R"))
    )
    (comp (ref "TP119")
      (value "TP10R")
      (footprint "TP10R")
      (description "Testpoint, Round 1.0mm Dia")
      (fields (field (name "ADDED BY") "Jeremy D") (field (name "CHECKED BY") "Paul B"))
      (libsource (lib "LEGACY_Rigado_AltiumLib") (part "TP_R"))
    )
    (comp (ref "TP120")
      (value "TP10R")
      (footprint "TP10R")
      (description "Testpoint, Round 1.0mm Dia")
      (fields (field (name "ADDED BY") "Jeremy D") (field (name "CHECKED BY") "Paul B"))
      (libsource (lib "LEGACY_Rigado_AltiumLib") (part "TP_R"))
    )
    (comp (ref "TP121")
      (value "TP10R")
      (footprint "TP10R")
      (description "Testpoint, Round 1.0mm Dia")
      (fields (field (name "ADDED BY") "Jeremy D") (field (name "CHECKED BY") "Paul B"))
      (libsource (lib "LEGACY_Rigado_AltiumLib") (part "TP_R"))
    )
    (comp (ref "TP122")
      (value "TP10R")
      (footprint "TP10R")
      (description "Testpoint, Round 1.0mm Dia")
      (fields (field (name "ADDED BY") "Jeremy D") (field (name "CHECKED BY") "Paul B"))
      (libsource (lib "LEGACY_Rigado_AltiumLib") (part "TP_R"))
    )
    (comp (ref "TP123")
      (value "TP10R")
      (footprint "TP10R")
      (description "Testpoint, Round 1.0mm Dia")
      (fields (field (name "ADDED BY") "Jeremy D") (field (name "CHECKED BY") "Paul B"))
      (libsource (lib "LEGACY_Rigado_AltiumLib") (part "TP_R"))
    )
    (comp (ref "TP124")
      (value "TP10R")
      (footprint "TP10R")
      (description "Testpoint, Round 1.0mm Dia")
      (fields (field (name "ADDED BY") "Jeremy D") (field (name "CHECKED BY") "Paul B"))
      (libsource (lib "LEGACY_Rigado_AltiumLib") (part "TP_R"))
    )
    (comp (ref "TP125")
      (value "TP10R")
      (footprint "TP10R")
      (description "Testpoint, Round 1.0mm Dia")
      (fields (field (name "ADDED BY") "Jeremy D") (field (name "CHECKED BY") "Paul B"))
      (libsource (lib "") (part "TP_R_1"))
    )
    (comp (ref "TP126")
      (value "TP10R")
      (footprint "TP10R")
      (description "Testpoint, Round 1.0mm Dia")
      (fields (field (name "ADDED BY") "Jeremy D") (field (name "CHECKED BY") "Paul B"))
      (libsource (lib "LEGACY_Rigado_AltiumLib") (part "TP_R"))
    )
    (comp (ref "U5")
      (value "UBXH06-0000120")
      (footprint "SOP65P400X110-8N")
      (description "Non-inverting Buffers & Line Drivers 3 Channels /SOT505/TSSOP8 1.65V to 5.5V")
      (fields
        (field (name "MANUFACTURER_PART_NUMBER") "74LVC3G07DP,125")
        (field (name "MOUSER PART NUMBER") "771-74LVC3G07DP-G")
        (field (name "ARROW PART NUMBER") "74LVC3G07DP,125")
        (field (name "OWNER") "Hozaifa Abdelgadir")
      )
      (libsource (lib "UBX_Arena") (part "74LVC3G07DP,125"))
    )
    (comp (ref "U6")
      (value "UBXH06-0000120")
      (footprint "SOP65P400X110-8N")
      (description "Non-inverting Buffers & Line Drivers 3 Channels /SOT505/TSSOP8 1.65V to 5.5V")
      (fields
        (field (name "MANUFACTURER_PART_NUMBER") "74LVC3G07DP,125")
        (field (name "MOUSER PART NUMBER") "771-74LVC3G07DP-G")
        (field (name "ARROW PART NUMBER") "74LVC3G07DP,125")
        (field (name "OWNER") "Hozaifa Abdelgadir")
      )
      (libsource (lib "UBX_Arena") (part "74LVC3G07DP,125"))
    )
    (comp (ref "U7")
      (value "UBXH06-0000120")
      (footprint "SOP65P400X110-8N")
      (description "Non-inverting Buffers & Line Drivers 3 Channels /SOT505/TSSOP8 1.65V to 5.5V")
      (fields
        (field (name "MANUFACTURER_PART_NUMBER") "74LVC3G07DP,125")
        (field (name "MOUSER PART NUMBER") "771-74LVC3G07DP-G")
        (field (name "ARROW PART NUMBER") "74LVC3G07DP,125")
        (field (name "OWNER") "Hozaifa Abdelgadir")
      )
      (libsource (lib "UBX_Arena") (part "74LVC3G07DP,125"))
    )
  )
  (nets
    (net (code "14") (name "+3V3") (class "Default")
      (node (ref "D10") (pin "2") (pinfunction "A_2") (pintype "passive"))
      (node (ref "D11") (pin "2") (pinfunction "A_2") (pintype "passive"))
      (node (ref "D12") (pin "2") (pinfunction "A_2") (pintype "passive"))
      (node (ref "D13") (pin "2") (pinfunction "A_2") (pintype "passive"))
      (node (ref "D14") (pin "2") (pinfunction "A_2") (pintype "passive"))
      (node (ref "D19") (pin "2") (pinfunction "A_2") (pintype "passive"))
      (node (ref "D9") (pin "2") (pinfunction "A_2") (pintype "passive"))
      (node (ref "J7") (pin "19") (pinfunction "19_19") (pintype "passive"))
      (node (ref "J8") (pin "26") (pinfunction "26_26") (pintype "passive"))
      (node (ref "RGB1") (pin "4") (pinfunction "A_4") (pintype "passive"))
      (node (ref "TP110") (pin "1") (pintype "passive"))
      (node (ref "TP63") (pin "1") (pintype "passive"))
    )
    (net (code "15") (name "+5V") (class "Default")
      (node (ref "J7") (pin "33") (pinfunction "33_33") (pintype "passive"))
      (node (ref "TP77") (pin "1") (pintype "passive"))
    )
    (net (code "16") (name "+Vin") (class "Default")
      (node (ref "J7") (pin "35") (pinfunction "35_35") (pintype "passive"))
      (node (ref "TP79") (pin "1") (pintype "passive"))
    )
    (net (code "17") (name "/Button0") (class "Default")
      (node (ref "J7") (pin "40") (pinfunction "40_40") (pintype "passive"))
      (node (ref "TP84") (pin "1") (pintype "passive"))
    )
    (net (code "18") (name "/Button1") (class "Default")
      (node (ref "J7") (pin "38") (pinfunction "38_38") (pintype "passive"))
      (node (ref "TP82") (pin "1") (pintype "passive"))
    )
    (net (code "19") (name "/Button2") (class "Default")
      (node (ref "J7") (pin "29") (pinfunction "29_29") (pintype "passive"))
      (node (ref "TP72") (pin "1") (pintype "passive"))
    )
    (net (code "20") (name "/Button3") (class "Default")
      (node (ref "J7") (pin "27") (pinfunction "27_27") (pintype "passive"))
      (node (ref "TP71") (pin "1") (pintype "passive"))
    )
    (net (code "21") (name "/CTS") (class "Default")
      (node (ref "R64") (pin "1") (pinfunction "1_1") (pintype "passive"))
      (node (ref "U5") (pin "5") (pinfunction "2Y_5") (pintype "passive"))
    )
    (net (code "22") (name "/DSR") (class "Default")
      (node (ref "R59") (pin "1") (pinfunction "1_1") (pintype "passive"))
      (node (ref "U5") (pin "7") (pinfunction "1Y_7") (pintype "passive"))
    )
    (net (code "23") (name "/DTR") (class "Default")
      (node (ref "R61") (pin "1") (pinfunction "1_1") (pintype "passive"))
      (node (ref "U5") (pin "2") (pinfunction "3Y_2") (pintype "passive"))
    )
    (net (code "24") (name "/GREEN") (class "Default")
      (node (ref "R72") (pin "1") (pinfunction "1_1") (pintype "passive"))
      (node (ref "U7") (pin "2") (pinfunction "3Y_2") (pintype "passive"))
    )
    (net (code "25") (name "/P0.00{slash}D_TX") (class "Default")
      (node (ref "J7") (pin "36") (pinfunction "36_36") (pintype "passive"))
      (node (ref "TP80") (pin "1") (pintype "passive"))
    )
    (net (code "26") (name "/P0.01{slash}D_RX") (class "Default")
      (node (ref "J7") (pin "34") (pinfunction "34_34") (pintype "passive"))
      (node (ref "TP78") (pin "1") (pintype "passive"))
    )
    (net (code "27") (name "/P0.02{slash}SW2") (class "Default")
      (node (ref "J7") (pin "32") (pinfunction "32_32") (pintype "passive"))
      (node (ref "TP76") (pin "1") (pintype "passive"))
    )
    (net (code "28") (name "/P0.03{slash}WAKE_UP") (class "Default")
      (node (ref "J7") (pin "26") (pinfunction "26_26") (pintype "passive"))
      (node (ref "TP70") (pin "1") (pintype "passive"))
    )
    (net (code "29") (name "/P0.04{slash}LED_GREEN") (class "Default")
      (node (ref "J7") (pin "30") (pinfunction "30_30") (pintype "passive"))
      (node (ref "R76") (pin "2") (pinfunction "2_2") (pintype "passive"))
      (node (ref "TP73") (pin "1") (pintype "passive"))
    )
    (net (code "30") (name "/P1.00") (class "Default")
      (node (ref "J8") (pin "3") (pinfunction "3_3") (pintype "passive"))
      (node (ref "TP86") (pin "1") (pintype "passive"))
    )
    (net (code "31") (name "/P1.01") (class "Default")
      (node (ref "J8") (pin "5") (pinfunction "5_5") (pintype "passive"))
      (node (ref "TP89") (pin "1") (pintype "passive"))
    )
    (net (code "32") (name "/P1.02") (class "Default")
      (node (ref "J8") (pin "7") (pinfunction "7_7") (pintype "passive"))
      (node (ref "TP91") (pin "1") (pintype "passive"))
    )
    (net (code "33") (name "/P1.03") (class "Default")
      (node (ref "J8") (pin "9") (pinfunction "9_9") (pintype "passive"))
      (node (ref "TP93") (pin "1") (pintype "passive"))
    )
    (net (code "34") (name "/P1.04{slash}URT1_TX") (class "Default")
      (node (ref "J7") (pin "16") (pinfunction "16_16") (pintype "passive"))
      (node (ref "TP60") (pin "1") (pintype "passive"))
    )
    (net (code "35") (name "/P1.05{slash}URT1_RX") (class "Default")
      (node (ref "J7") (pin "18") (pinfunction "18_18") (pintype "passive"))
      (node (ref "TP62") (pin "1") (pintype "passive"))
    )
    (net (code "36") (name "/P1.06{slash}URT1_RTS") (class "Default")
      (node (ref "J7") (pin "20") (pinfunction "20_20") (pintype "passive"))
      (node (ref "TP64") (pin "1") (pintype "passive"))
    )
    (net (code "37") (name "/P1.07{slash}URT1_CTS") (class "Default")
      (node (ref "J7") (pin "22") (pinfunction "22_22") (pintype "passive"))
      (node (ref "TP65") (pin "1") (pintype "passive"))
    )
    (net (code "38") (name "/P1.08{slash}EXTREF") (class "Default")
      (node (ref "J8") (pin "11") (pinfunction "11_11") (pintype "passive"))
      (node (ref "TP94") (pin "1") (pintype "passive"))
    )
    (net (code "39") (name "/P1.09{slash}SW1") (class "Default")
      (node (ref "J8") (pin "13") (pinfunction "13_13") (pintype "passive"))
      (node (ref "TP97") (pin "1") (pintype "passive"))
    )
    (net (code "40") (name "/P1.10{slash}LED_BLUE") (class "Default")
      (node (ref "J8") (pin "2") (pinfunction "2_2") (pintype "passive"))
      (node (ref "R73") (pin "2") (pinfunction "2_2") (pintype "passive"))
      (node (ref "TP85") (pin "1") (pintype "passive"))
    )
    (net (code "41") (name "/P1.11{slash}I2C_SCL") (class "Default")
      (node (ref "J8") (pin "4") (pinfunction "4_4") (pintype "passive"))
      (node (ref "TP87") (pin "1") (pintype "passive"))
    )
    (net (code "42") (name "/P1.12{slash}I2C_SDA") (class "Default")
      (node (ref "J8") (pin "6") (pinfunction "6_6") (pintype "passive"))
      (node (ref "TP90") (pin "1") (pintype "passive"))
    )
    (net (code "43") (name "/P1.13{slash}LED_RED") (class "Default")
      (node (ref "J8") (pin "8") (pinfunction "8_8") (pintype "passive"))
      (node (ref "R70") (pin "2") (pinfunction "2_2") (pintype "passive"))
      (node (ref "TP92") (pin "1") (pintype "passive"))
    )
    (net (code "44") (name "/P1.14{slash}WAKE-HOST{slash}UART1_DTR") (class "Default")
      (node (ref "J7") (pin "24") (pinfunction "24_24") (pintype "passive"))
      (node (ref "TP67") (pin "1") (pintype "passive"))
    )
    (net (code "45") (name "/P2.00") (class "Default")
      (node (ref "J7") (pin "3") (pinfunction "3_3") (pintype "passive"))
      (node (ref "TP46") (pin "1") (pintype "passive"))
    )
    (net (code "46") (name "/P2.01") (class "Default")
      (node (ref "J7") (pin "4") (pinfunction "4_4") (pintype "passive"))
      (node (ref "TP47") (pin "1") (pintype "passive"))
    )
    (net (code "47") (name "/P2.02") (class "Default")
      (node (ref "J7") (pin "5") (pinfunction "5_5") (pintype "passive"))
      (node (ref "TP49") (pin "1") (pintype "passive"))
    )
    (net (code "48") (name "/P2.03") (class "Default")
      (node (ref "J7") (pin "6") (pinfunction "6_6") (pintype "passive"))
      (node (ref "TP50") (pin "1") (pintype "passive"))
    )
    (net (code "49") (name "/P2.04") (class "Default")
      (node (ref "J7") (pin "7") (pinfunction "7_7") (pintype "passive"))
      (node (ref "TP51") (pin "1") (pintype "passive"))
    )
    (net (code "50") (name "/P2.05") (class "Default")
      (node (ref "J7") (pin "8") (pinfunction "8_8") (pintype "passive"))
      (node (ref "TP52") (pin "1") (pintype "passive"))
    )
    (net (code "51") (name "/P2.06{slash}SPI1_CLK") (class "Default")
      (node (ref "J7") (pin "9") (pinfunction "9_9") (pintype "passive"))
      (node (ref "TP53") (pin "1") (pintype "passive"))
    )
    (net (code "52") (name "/P2.07{slash}SPI2_CS1{slash}SPI_DCX") (class "Default")
      (node (ref "J7") (pin "12") (pinfunction "12_12") (pintype "passive"))
      (node (ref "R74") (pin "2") (pinfunction "2_2") (pintype "passive"))
      (node (ref "TP55") (pin "1") (pintype "passive"))
    )
    (net (code "53") (name "/P2.08{slash}SPI1_MOSI") (class "Default")
      (node (ref "J7") (pin "11") (pinfunction "11_11") (pintype "passive"))
      (node (ref "TP54") (pin "1") (pintype "passive"))
    )
    (net (code "54") (name "/P2.09{slash}SPI1_MISO") (class "Default")
      (node (ref "J7") (pin "14") (pinfunction "14_14") (pintype "passive"))
      (node (ref "R69") (pin "2") (pinfunction "2_2") (pintype "passive"))
      (node (ref "TP58") (pin "1") (pintype "passive"))
    )
    (net (code "55") (name "/P2.10{slash}SPI1_CS0") (class "Default")
      (node (ref "J7") (pin "13") (pinfunction "13_13") (pintype "passive"))
      (node (ref "TP57") (pin "1") (pintype "passive"))
    )
    (net (code "56") (name "/RTS") (class "Default")
      (node (ref "R66") (pin "1") (pinfunction "1_1") (pintype "passive"))
      (node (ref "U6") (pin "7") (pinfunction "1Y_7") (pintype "passive"))
    )
    (net (code "57") (name "/RXD") (class "Default")
      (node (ref "R67") (pin "1") (pinfunction "1_1") (pintype "passive"))
      (node (ref "U6") (pin "2") (pinfunction "3Y_2") (pintype "passive"))
    )
    (net (code "58") (name "/SWD_CLK_NORA") (class "Default")
      (node (ref "J8") (pin "22") (pinfunction "22_22") (pintype "passive"))
      (node (ref "TP105") (pin "1") (pintype "passive"))
    )
    (net (code "59") (name "/SWD_IO_NORA") (class "Default")
      (node (ref "J8") (pin "24") (pinfunction "24_24") (pintype "passive"))
      (node (ref "TP107") (pin "1") (pintype "passive"))
    )
    (net (code "60") (name "/TXD") (class "Default")
      (node (ref "R68") (pin "1") (pinfunction "1_1") (pintype "passive"))
      (node (ref "U6") (pin "5") (pinfunction "2Y_5") (pintype "passive"))
    )
    (net (code "61") (name "/UART0_OBD-CTS") (class "Default")
      (node (ref "J7") (pin "25") (pinfunction "25_25") (pintype "passive"))
      (node (ref "TP69") (pin "1") (pintype "passive"))
    )
    (net (code "62") (name "/UART0_OBD-RTS") (class "Default")
      (node (ref "J7") (pin "31") (pinfunction "31_31") (pintype "passive"))
      (node (ref "TP75") (pin "1") (pintype "passive"))
    )
    (net (code "63") (name "/UART1-CTS") (class "Default")
      (node (ref "R60") (pin "2") (pinfunction "2_2") (pintype "passive"))
    )
    (net (code "64") (name "/UART1-DSR") (class "Default")
      (node (ref "R57") (pin "2") (pinfunction "2_2") (pintype "passive"))
    )
    (net (code "65") (name "/UART1-DTR") (class "Default")
      (node (ref "R58") (pin "2") (pinfunction "2_2") (pintype "passive"))
    )
    (net (code "66") (name "/UART1-RTS") (class "Default")
      (node (ref "R62") (pin "2") (pinfunction "2_2") (pintype "passive"))
    )
    (net (code "67") (name "/UART1-RXD") (class "Default")
      (node (ref "R63") (pin "2") (pinfunction "2_2") (pintype "passive"))
    )
    (net (code "68") (name "/UART1-TXD") (class "Default")
      (node (ref "R65") (pin "2") (pinfunction "2_2") (pintype "passive"))
    )
    (net (code "69") (name "/UART1_OBD-CTS") (class "Default")
      (node (ref "J8") (pin "36") (pinfunction "36_36") (pintype "passive"))
      (node (ref "TP120") (pin "1") (pintype "passive"))
    )
    (net (code "70") (name "/UART1_OBD-RTS") (class "Default")
      (node (ref "J8") (pin "34") (pinfunction "34_34") (pintype "passive"))
      (node (ref "TP118") (pin "1") (pintype "passive"))
    )
    (net (code "71") (name "/UART1_OBD-RX") (class "Default")
      (node (ref "J8") (pin "32") (pinfunction "32_32") (pintype "passive"))
      (node (ref "TP116") (pin "1") (pintype "passive"))
    )
    (net (code "72") (name "/UART1_OBD-TX") (class "Default")
      (node (ref "J8") (pin "30") (pinfunction "30_30") (pintype "passive"))
      (node (ref "TP113") (pin "1") (pintype "passive"))
    )
    (net (code "73") (name "/nRESET") (class "Default")
      (node (ref "J8") (pin "20") (pinfunction "20_20") (pintype "passive"))
      (node (ref "TP104") (pin "1") (pintype "passive"))
    )
    (net (code "87") (name "GND") (class "Default")
      (node (ref "J7") (pin "1") (pinfunction "1_1") (pintype "passive"))
      (node (ref "J7") (pin "10") (pinfunction "10_10") (pintype "passive"))
      (node (ref "J7") (pin "21") (pinfunction "21_21") (pintype "passive"))
      (node (ref "J7") (pin "28") (pinfunction "28_28") (pintype "passive"))
      (node (ref "J8") (pin "1") (pinfunction "1_1") (pintype "passive"))
      (node (ref "J8") (pin "10") (pinfunction "10_10") (pintype "passive"))
      (node (ref "J8") (pin "21") (pinfunction "21_21") (pintype "passive"))
      (node (ref "J8") (pin "28") (pinfunction "28_28") (pintype "passive"))
      (node (ref "R77") (pin "1") (pinfunction "1_1") (pintype "passive"))
      (node (ref "TP108") (pin "1") (pintype "passive"))
      (node (ref "TP114") (pin "1") (pintype "passive"))
      (node (ref "TP38") (pin "1") (pintype "passive"))
      (node (ref "TP44") (pin "1") (pintype "passive"))
      (node (ref "TP48") (pin "1") (pintype "passive"))
      (node (ref "TP56") (pin "1") (pintype "passive"))
      (node (ref "TP68") (pin "1") (pintype "passive"))
      (node (ref "TP74") (pin "1") (pintype "passive"))
      (node (ref "TP88") (pin "1") (pintype "passive"))
      (node (ref "TP96") (pin "1") (pintype "passive"))
      (node (ref "U5") (pin "4") (pinfunction "GND_4") (pintype "passive"))
      (node (ref "U6") (pin "4") (pinfunction "GND_4") (pintype "passive"))
      (node (ref "U7") (pin "4") (pinfunction "GND_4") (pintype "passive"))
    )
    (net (code "88") (name "Net-(D9-C)") (class "Default")
      (node (ref "D9") (pin "1") (pinfunction "C_1") (pintype "passive"))
      (node (ref "R59") (pin "2") (pinfunction "2_2") (pintype "passive"))
    )
    (net (code "89") (name "Net-(D10-C)") (class "Default")
      (node (ref "D10") (pin "1") (pinfunction "C_1") (pintype "passive"))
      (node (ref "R61") (pin "2") (pinfunction "2_2") (pintype "passive"))
    )
    (net (code "90") (name "Net-(D11-C)") (class "Default")
      (node (ref "D11") (pin "1") (pinfunction "C_1") (pintype "passive"))
      (node (ref "R64") (pin "2") (pinfunction "2_2") (pintype "passive"))
    )
    (net (code "91") (name "Net-(D12-C)") (class "Default")
      (node (ref "D12") (pin "1") (pinfunction "C_1") (pintype "passive"))
      (node (ref "R66") (pin "2") (pinfunction "2_2") (pintype "passive"))
    )
    (net (code "92") (name "Net-(D13-C)") (class "Default")
      (node (ref "D13") (pin "1") (pinfunction "C_1") (pintype "passive"))
      (node (ref "R67") (pin "2") (pinfunction "2_2") (pintype "passive"))
    )
    (net (code "93") (name "Net-(D14-C)") (class "Default")
      (node (ref "D14") (pin "1") (pinfunction "C_1") (pintype "passive"))
      (node (ref "R68") (pin "2") (pinfunction "2_2") (pintype "passive"))
    )
    (net (code "94") (name "Net-(D19-C)") (class "Default")
      (node (ref "D19") (pin "1") (pinfunction "C_1") (pintype "passive"))
      (node (ref "R77") (pin "2") (pinfunction "2_2") (pintype "passive"))
    )
    (net (code "95") (name "Net-(J7-Pad2)") (class "Default")
      (node (ref "J7") (pin "2") (pinfunction "2_2") (pintype "passive"))
      (node (ref "TP45") (pin "1") (pintype "passive"))
    )
    (net (code "96") (name "Net-(J7-Pad15)") (class "Default")
      (node (ref "J7") (pin "15") (pinfunction "15_15") (pintype "passive"))
      (node (ref "TP59") (pin "1") (pintype "passive"))
    )
    (net (code "97") (name "Net-(J7-Pad17)") (class "Default")
      (node (ref "J7") (pin "17") (pinfunction "17_17") (pintype "passive"))
      (node (ref "TP61") (pin "1") (pintype "passive"))
    )
    (net (code "98") (name "Net-(J7-Pad23)") (class "Default")
      (node (ref "J7") (pin "23") (pinfunction "23_23") (pintype "passive"))
      (node (ref "TP66") (pin "1") (pintype "passive"))
    )
    (net (code "99") (name "Net-(J8-Pad12)") (class "Default")
      (node (ref "J8") (pin "12") (pinfunction "12_12") (pintype "passive"))
      (node (ref "TP95") (pin "1") (pintype "passive"))
    )
    (net (code "100") (name "Net-(J8-Pad14)") (class "Default")
      (node (ref "J8") (pin "14") (pinfunction "14_14") (pintype "passive"))
      (node (ref "TP98") (pin "1") (pintype "passive"))
    )
    (net (code "101") (name "Net-(J8-Pad15)") (class "Default")
      (node (ref "J8") (pin "15") (pinfunction "15_15") (pintype "passive"))
      (node (ref "TP99") (pin "1") (pintype "passive"))
    )
    (net (code "102") (name "Net-(J8-Pad16)") (class "Default")
      (node (ref "J8") (pin "16") (pinfunction "16_16") (pintype "passive"))
      (node (ref "TP100") (pin "1") (pintype "passive"))
    )
    (net (code "103") (name "Net-(J8-Pad17)") (class "Default")
      (node (ref "J8") (pin "17") (pinfunction "17_17") (pintype "passive"))
      (node (ref "TP101") (pin "1") (pintype "passive"))
    )
    (net (code "104") (name "Net-(J8-Pad18)") (class "Default")
      (node (ref "J8") (pin "18") (pinfunction "18_18") (pintype "passive"))
      (node (ref "TP102") (pin "1") (pintype "passive"))
    )
    (net (code "105") (name "Net-(J8-Pad19)") (class "Default")
      (node (ref "J8") (pin "19") (pinfunction "19_19") (pintype "passive"))
      (node (ref "TP103") (pin "1") (pintype "passive"))
    )
    (net (code "106") (name "Net-(J8-Pad23)") (class "Default")
      (node (ref "J8") (pin "23") (pinfunction "23_23") (pintype "passive"))
      (node (ref "TP106") (pin "1") (pintype "passive"))
    )
    (net (code "107") (name "Net-(J8-Pad25)") (class "Default")
      (node (ref "J8") (pin "25") (pinfunction "25_25") (pintype "passive"))
      (node (ref "TP109") (pin "1") (pintype "passive"))
    )
    (net (code "108") (name "Net-(J8-Pad27)") (class "Default")
      (node (ref "J8") (pin "27") (pinfunction "27_27") (pintype "passive"))
      (node (ref "TP111") (pin "1") (pintype "passive"))
    )
    (net (code "109") (name "Net-(J8-Pad29)") (class "Default")
      (node (ref "J8") (pin "29") (pinfunction "29_29") (pintype "passive"))
      (node (ref "TP112") (pin "1") (pintype "passive"))
    )
    (net (code "110") (name "Net-(J8-Pad31)") (class "Default")
      (node (ref "J8") (pin "31") (pinfunction "31_31") (pintype "passive"))
      (node (ref "TP115") (pin "1") (pintype "passive"))
    )
    (net (code "111") (name "Net-(J8-Pad33)") (class "Default")
      (node (ref "J8") (pin "33") (pinfunction "33_33") (pintype "passive"))
      (node (ref "TP117") (pin "1") (pintype "passive"))
    )
    (net (code "112") (name "Net-(J8-Pad35)") (class "Default")
      (node (ref "J8") (pin "35") (pinfunction "35_35") (pintype "passive"))
      (node (ref "TP119") (pin "1") (pintype "passive"))
    )
    (net (code "113") (name "Net-(J8-Pad37)") (class "Default")
      (node (ref "J8") (pin "37") (pinfunction "37_37") (pintype "passive"))
      (node (ref "TP121") (pin "1") (pintype "passive"))
    )
    (net (code "114") (name "Net-(J8-Pad38)") (class "Default")
      (node (ref "J8") (pin "38") (pinfunction "38_38") (pintype "passive"))
      (node (ref "TP122") (pin "1") (pintype "passive"))
    )
    (net (code "115") (name "Net-(J8-Pad39)") (class "Default")
      (node (ref "J8") (pin "39") (pinfunction "39_39") (pintype "passive"))
      (node (ref "TP123") (pin "1") (pintype "passive"))
    )
    (net (code "116") (name "Net-(J8-Pad40)") (class "Default")
      (node (ref "J8") (pin "40") (pinfunction "40_40") (pintype "passive"))
      (node (ref "TP124") (pin "1") (pintype "passive"))
    )
    (net (code "117") (name "Net-(RGB1-B)") (class "Default")
      (node (ref "R75") (pin "2") (pinfunction "2_2") (pintype "passive"))
      (node (ref "RGB1") (pin "3") (pinfunction "B_3") (pintype "passive"))
    )
    (net (code "118") (name "Net-(RGB1-G)") (class "Default")
      (node (ref "R72") (pin "2") (pinfunction "2_2") (pintype "passive"))
      (node (ref "RGB1") (pin "2") (pinfunction "G_2") (pintype "passive"))
    )
    (net (code "119") (name "Net-(RGB1-R)") (class "Default")
      (node (ref "R71") (pin "2") (pinfunction "2_2") (pintype "passive"))
      (node (ref "RGB1") (pin "1") (pinfunction "R_1") (pintype "passive"))
    )
    (net (code "120") (name "Net-(U5-1A)") (class "Default")
      (node (ref "R57") (pin "1") (pinfunction "1_1") (pintype "passive"))
      (node (ref "U5") (pin "1") (pinfunction "1A_1") (pintype "passive"))
    )
    (net (code "121") (name "Net-(U5-2A)") (class "Default")
      (node (ref "R60") (pin "1") (pinfunction "1_1") (pintype "passive"))
      (node (ref "U5") (pin "3") (pinfunction "2A_3") (pintype "passive"))
    )
    (net (code "122") (name "Net-(U5-3A)") (class "Default")
      (node (ref "R58") (pin "1") (pinfunction "1_1") (pintype "passive"))
      (node (ref "U5") (pin "6") (pinfunction "3A_6") (pintype "passive"))
    )
    (net (code "123") (name "Net-(U6-1A)") (class "Default")
      (node (ref "R62") (pin "1") (pinfunction "1_1") (pintype "passive"))
      (node (ref "U6") (pin "1") (pinfunction "1A_1") (pintype "passive"))
    )
    (net (code "124") (name "Net-(U6-2A)") (class "Default")
      (node (ref "R65") (pin "1") (pinfunction "1_1") (pintype "passive"))
      (node (ref "U6") (pin "3") (pinfunction "2A_3") (pintype "passive"))
    )
    (net (code "125") (name "Net-(U6-3A)") (class "Default")
      (node (ref "R63") (pin "1") (pinfunction "1_1") (pintype "passive"))
      (node (ref "U6") (pin "6") (pinfunction "3A_6") (pintype "passive"))
    )
    (net (code "126") (name "Net-(U7-1A)") (class "Default")
      (node (ref "R222") (pin "2") (pinfunction "2_2") (pintype "passive"))
      (node (ref "R69") (pin "1") (pinfunction "1_1") (pintype "passive"))
      (node (ref "R70") (pin "1") (pinfunction "1_1") (pintype "passive"))
      (node (ref "U7") (pin "1") (pinfunction "1A_1") (pintype "passive"))
    )
    (net (code "127") (name "Net-(U7-1Y)") (class "Default")
      (node (ref "R71") (pin "1") (pinfunction "1_1") (pintype "passive"))
      (node (ref "U7") (pin "7") (pinfunction "1Y_7") (pintype "passive"))
    )
    (net (code "128") (name "Net-(U7-2A)") (class "Default")
      (node (ref "R223") (pin "2") (pinfunction "2_2") (pintype "passive"))
      (node (ref "R73") (pin "1") (pinfunction "1_1") (pintype "passive"))
      (node (ref "U7") (pin "3") (pinfunction "2A_3") (pintype "passive"))
    )
    (net (code "129") (name "Net-(U7-2Y)") (class "Default")
      (node (ref "R75") (pin "1") (pinfunction "1_1") (pintype "passive"))
      (node (ref "U7") (pin "5") (pinfunction "2Y_5") (pintype "passive"))
    )
    (net (code "130") (name "Net-(U7-3A)") (class "Default")
      (node (ref "R224") (pin "2") (pinfunction "2_2") (pintype "passive"))
      (node (ref "R74") (pin "1") (pinfunction "1_1") (pintype "passive"))
      (node (ref "R76") (pin "1") (pinfunction "1_1") (pintype "passive"))
      (node (ref "U7") (pin "6") (pinfunction "3A_6") (pintype "passive"))
    )
    (net (code "131") (name "VBUS") (class "Default")
      (node (ref "J7") (pin "39") (pinfunction "39_39") (pintype "passive"))
      (node (ref "TP83") (pin "1") (pintype "passive"))
    )
    (net (code "132") (name "VDDIO_Periph") (class "Default")
      (node (ref "J7") (pin "37") (pinfunction "37_37") (pintype "passive"))
      (node (ref "R222") (pin "1") (pinfunction "1_1") (pintype "passive"))
      (node (ref "R223") (pin "1") (pinfunction "1_1") (pintype "passive"))
      (node (ref "R224") (pin "1") (pinfunction "1_1") (pintype "passive"))
      (node (ref "TP81") (pin "1") (pintype "passive"))
      (node (ref "U5") (pin "8") (pinfunction "VCC_8") (pintype "passive"))
      (node (ref "U6") (pin "8") (pinfunction "VCC_8") (pintype "passive"))
      (node (ref "U7") (pin "8") (pinfunction "VCC_8") (pintype "passive"))
    )
    (net (code "133") (name "unconnected-(TP2-Pad1)") (class "Default")
      (node (ref "TP2") (pin "1") (pintype "passive+no_connect"))
    )
    (net (code "134") (name "unconnected-(TP3-Pad1)") (class "Default")
      (node (ref "TP3") (pin "1") (pintype "passive+no_connect"))
    )
    (net (code "135") (name "unconnected-(TP6-Pad1)") (class "Default")
      (node (ref "TP6") (pin "1") (pintype "passive+no_connect"))
    )
    (net (code "136") (name "unconnected-(TP7-Pad1)") (class "Default")
      (node (ref "TP7") (pin "1") (pintype "passive+no_connect"))
    )
    (net (code "137") (name "unconnected-(TP8-Pad1)") (class "Default")
      (node (ref "TP8") (pin "1") (pintype "passive+no_connect"))
    )
    (net (code "138") (name "unconnected-(TP9-Pad1)") (class "Default")
      (node (ref "TP9") (pin "1") (pintype "passive+no_connect"))
    )
    (net (code "139") (name "unconnected-(TP10-Pad1)") (class "Default")
      (node (ref "TP10") (pin "1") (pintype "passive+no_connect"))
    )
    (net (code "140") (name "unconnected-(TP11-Pad1)") (class "Default")
      (node (ref "TP11") (pin "1") (pintype "passive+no_connect"))
    )
    (net (code "141") (name "unconnected-(TP12-Pad1)") (class "Default")
      (node (ref "TP12") (pin "1") (pintype "passive+no_connect"))
    )
    (net (code "142") (name "unconnected-(TP13-Pad1)") (class "Default")
      (node (ref "TP13") (pin "1") (pintype "passive+no_connect"))
    )
    (net (code "143") (name "unconnected-(TP14-Pad1)") (class "Default")
      (node (ref "TP14") (pin "1") (pintype "passive+no_connect"))
    )
    (net (code "144") (name "unconnected-(TP15-Pad1)") (class "Default")
      (node (ref "TP15") (pin "1") (pintype "passive+no_connect"))
    )
    (net (code "145") (name "unconnected-(TP18-Pad1)") (class "Default")
      (node (ref "TP18") (pin "1") (pintype "passive+no_connect"))
    )
    (net (code "146") (name "unconnected-(TP19-Pad1)") (class "Default")
      (node (ref "TP19") (pin "1") (pintype "passive+no_connect"))
    )
    (net (code "147") (name "unconnected-(TP20-Pad1)") (class "Default")
      (node (ref "TP20") (pin "1") (pintype "passive+no_connect"))
    )
    (net (code "148") (name "unconnected-(TP21-Pad1)") (class "Default")
      (node (ref "TP21") (pin "1") (pintype "passive+no_connect"))
    )
    (net (code "149") (name "unconnected-(TP22-Pad1)") (class "Default")
      (node (ref "TP22") (pin "1") (pintype "passive+no_connect"))
    )
    (net (code "150") (name "unconnected-(TP23-Pad1)") (class "Default")
      (node (ref "TP23") (pin "1") (pintype "passive+no_connect"))
    )
    (net (code "151") (name "unconnected-(TP24-Pad1)") (class "Default")
      (node (ref "TP24") (pin "1") (pintype "passive+no_connect"))
    )
    (net (code "152") (name "unconnected-(TP25-Pad1)") (class "Default")
      (node (ref "TP25") (pin "1") (pintype "passive+no_connect"))
    )
    (net (code "153") (name "unconnected-(TP32-Pad1)") (class "Default")
      (node (ref "TP32") (pin "1") (pintype "passive+no_connect"))
    )
    (net (code "154") (name "unconnected-(TP33-Pad1)") (class "Default")
      (node (ref "TP33") (pin "1") (pintype "passive+no_connect"))
    )
    (net (code "155") (name "unconnected-(TP34-Pad1)") (class "Default")
      (node (ref "TP34") (pin "1") (pintype "passive+no_connect"))
    )
    (net (code "156") (name "unconnected-(TP35-Pad1)") (class "Default")
      (node (ref "TP35") (pin "1") (pintype "passive+no_connect"))
    )
    (net (code "157") (name "unconnected-(TP39-Pad1)") (class "Default")
      (node (ref "TP39") (pin "1") (pintype "passive+no_connect"))
    )
    (net (code "158") (name "unconnected-(TP40-Pad1)") (class "Default")
      (node (ref "TP40") (pin "1") (pintype "passive+no_connect"))
    )
    (net (code "159") (name "unconnected-(TP41-Pad1)") (class "Default")
      (node (ref "TP41") (pin "1") (pintype "passive+no_connect"))
    )
    (net (code "160") (name "unconnected-(TP125-Pad1)") (class "Default")
      (node (ref "TP125") (pin "1") (pintype "passive+no_connect"))
    )
    (net (code "161") (name "unconnected-(TP126-Pad1)") (class "Default")
      (node (ref "TP126") (pin "1") (pintype "passive+no_connect"))
    )
  )
)
